# Day0_UmarAlFaruqi_13215057.net
KiCad netlist of a schematic drawn in EAGLE
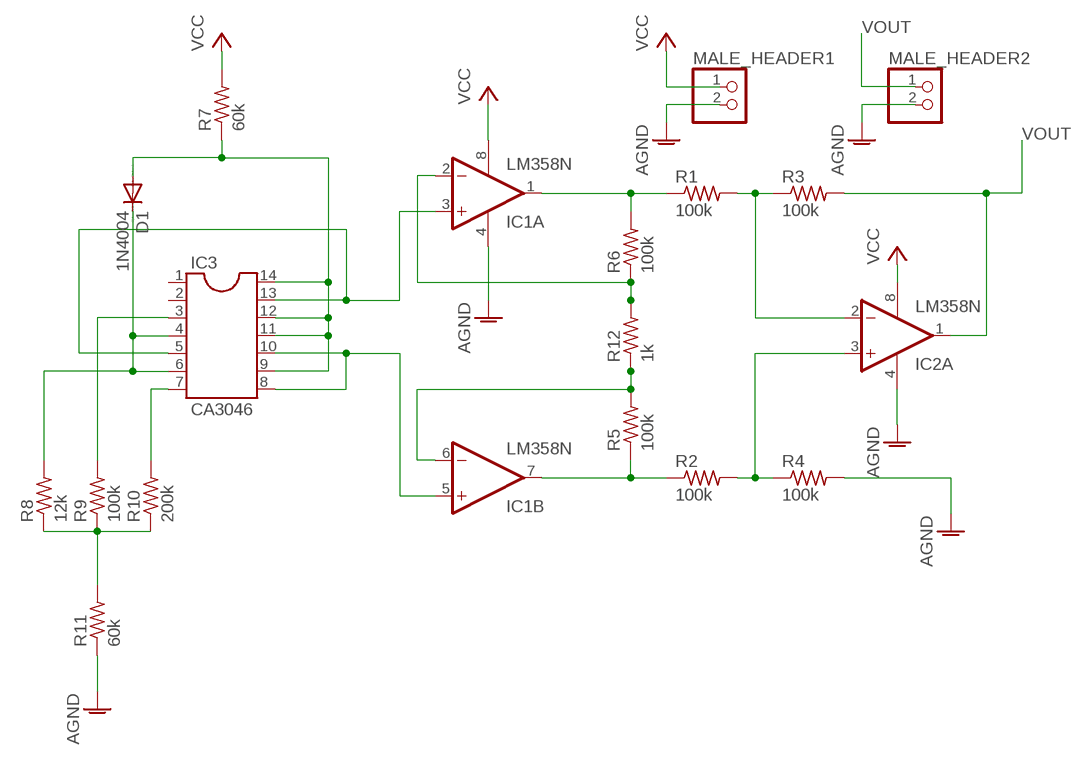
[diagram p0: schematic, sheet 1]

(export (version "E")
  (design (tool "Eeschema 10.0.6"))
  (components
    (comp (ref "D1")
      (value "1N4004")
      (footprint "eagle-import:DO41-10")
      (libsource (lib "eagle-import") (part "1N4004"))
    )
    (comp (ref "IC1")
      (value "LM358N")
      (footprint "eagle-import:DIL08")
      (libsource (lib "eagle-import") (part "LM358N"))
    )
    (comp (ref "IC2")
      (value "LM358N")
      (footprint "eagle-import:DIL08")
      (libsource (lib "eagle-import") (part "LM358N"))
    )
    (comp (ref "IC3")
      (value "CA3046")
      (footprint "eagle-import:DIL14")
      (libsource (lib "eagle-import") (part "DIL14"))
    )
    (comp (ref "MALE_HEADER1")
      (value "PINHD-1X2")
      (footprint "eagle-import:1X02")
      (libsource (lib "eagle-import") (part "PINHD-1X2"))
    )
    (comp (ref "MALE_HEADER2")
      (value "PINHD-1X2")
      (footprint "eagle-import:1X02")
      (libsource (lib "eagle-import") (part "PINHD-1X2"))
    )
    (comp (ref "R1")
      (value "100k")
      (footprint "eagle-import:0204V")
      (libsource (lib "eagle-import") (part "R-US_0204/2V"))
    )
    (comp (ref "R2")
      (value "100k")
      (footprint "eagle-import:0204V")
      (libsource (lib "eagle-import") (part "R-US_0204/2V"))
    )
    (comp (ref "R3")
      (value "100k")
      (footprint "eagle-import:0204V")
      (libsource (lib "eagle-import") (part "R-US_0204/2V"))
    )
    (comp (ref "R4")
      (value "100k")
      (footprint "eagle-import:0204V")
      (libsource (lib "eagle-import") (part "R-US_0204/2V"))
    )
    (comp (ref "R5")
      (value "100k")
      (footprint "eagle-import:0204V")
      (libsource (lib "eagle-import") (part "R-US_0204/2V"))
    )
    (comp (ref "R6")
      (value "100k")
      (footprint "eagle-import:0204V")
      (libsource (lib "eagle-import") (part "R-US_0204/2V"))
    )
    (comp (ref "R7")
      (value "60k")
      (footprint "eagle-import:0204V")
      (libsource (lib "eagle-import") (part "R-US_0204/2V"))
    )
    (comp (ref "R8")
      (value "12k")
      (footprint "eagle-import:0204V")
      (libsource (lib "eagle-import") (part "R-US_0204/2V"))
    )
    (comp (ref "R9")
      (value "100k")
      (footprint "eagle-import:0204V")
      (libsource (lib "eagle-import") (part "R-US_0204/2V"))
    )
    (comp (ref "R10")
      (value "200k")
      (footprint "eagle-import:0204V")
      (libsource (lib "eagle-import") (part "R-US_0204/2V"))
    )
    (comp (ref "R11")
      (value "60k")
      (footprint "eagle-import:0204V")
      (libsource (lib "eagle-import") (part "R-US_0204/2V"))
    )
    (comp (ref "R12")
      (value "1k")
      (footprint "eagle-import:0204V")
      (libsource (lib "eagle-import") (part "R-US_0204/2V"))
    )
  )
  (nets
    (net (code "1") (name "/VOUT") (class "Default")
      (node (ref "IC2") (pin "1") (pinfunction "OUT_1") (pintype "output"))
      (node (ref "MALE_HEADER2") (pin "1") (pinfunction "1_1") (pintype "passive"))
      (node (ref "R3") (pin "2") (pinfunction "2_2") (pintype "passive"))
    )
    (net (code "2") (name "AGND") (class "Default")
      (node (ref "IC1") (pin "4") (pinfunction "V-_4") (pintype "power_in"))
      (node (ref "IC2") (pin "4") (pinfunction "V-_4") (pintype "power_in"))
      (node (ref "MALE_HEADER1") (pin "2") (pinfunction "2_2") (pintype "passive"))
      (node (ref "MALE_HEADER2") (pin "2") (pinfunction "2_2") (pintype "passive"))
      (node (ref "R11") (pin "1") (pinfunction "1_1") (pintype "passive"))
      (node (ref "R4") (pin "2") (pinfunction "2_2") (pintype "passive"))
    )
    (net (code "3") (name "Net-(D1-PadA)") (class "Default")
      (node (ref "D1") (pin "A") (pinfunction "A_A") (pintype "passive"))
      (node (ref "IC3") (pin "11") (pinfunction "11_11") (pintype "passive"))
      (node (ref "IC3") (pin "12") (pinfunction "12_12") (pintype "passive"))
      (node (ref "IC3") (pin "14") (pinfunction "14_14") (pintype "passive"))
      (node (ref "IC3") (pin "9") (pinfunction "9_9") (pintype "passive"))
      (node (ref "R7") (pin "1") (pinfunction "1_1") (pintype "passive"))
    )
    (net (code "4") (name "Net-(D1-PadC)") (class "Default")
      (node (ref "D1") (pin "C") (pinfunction "C_C") (pintype "passive"))
      (node (ref "IC3") (pin "4") (pinfunction "4_4") (pintype "passive"))
      (node (ref "IC3") (pin "6") (pinfunction "6_6") (pintype "passive"))
      (node (ref "R8") (pin "2") (pinfunction "2_2") (pintype "passive"))
    )
    (net (code "5") (name "Net-(IC1A-+IN)") (class "Default")
      (node (ref "IC1") (pin "3") (pinfunction "+IN_3") (pintype "input"))
      (node (ref "IC3") (pin "13") (pinfunction "13_13") (pintype "passive"))
      (node (ref "IC3") (pin "5") (pinfunction "5_5") (pintype "passive"))
    )
    (net (code "6") (name "Net-(IC1A--IN)") (class "Default")
      (node (ref "IC1") (pin "2") (pinfunction "-IN_2") (pintype "input"))
      (node (ref "R12") (pin "2") (pinfunction "2_2") (pintype "passive"))
      (node (ref "R6") (pin "1") (pinfunction "1_1") (pintype "passive"))
    )
    (net (code "7") (name "Net-(IC1A-OUT)") (class "Default")
      (node (ref "IC1") (pin "1") (pinfunction "OUT_1") (pintype "output"))
      (node (ref "R1") (pin "1") (pinfunction "1_1") (pintype "passive"))
      (node (ref "R6") (pin "2") (pinfunction "2_2") (pintype "passive"))
    )
    (net (code "8") (name "Net-(IC1B-+IN)") (class "Default")
      (node (ref "IC1") (pin "5") (pinfunction "+IN_5") (pintype "input"))
      (node (ref "IC3") (pin "10") (pinfunction "10_10") (pintype "passive"))
      (node (ref "IC3") (pin "8") (pinfunction "8_8") (pintype "passive"))
    )
    (net (code "9") (name "Net-(IC1B--IN)") (class "Default")
      (node (ref "IC1") (pin "6") (pinfunction "-IN_6") (pintype "input"))
      (node (ref "R12") (pin "1") (pinfunction "1_1") (pintype "passive"))
      (node (ref "R5") (pin "2") (pinfunction "2_2") (pintype "passive"))
    )
    (net (code "10") (name "Net-(IC1B-OUT)") (class "Default")
      (node (ref "IC1") (pin "7") (pinfunction "OUT_7") (pintype "output"))
      (node (ref "R2") (pin "1") (pinfunction "1_1") (pintype "passive"))
      (node (ref "R5") (pin "1") (pinfunction "1_1") (pintype "passive"))
    )
    (net (code "11") (name "Net-(IC2A-+IN)") (class "Default")
      (node (ref "IC2") (pin "3") (pinfunction "+IN_3") (pintype "input"))
      (node (ref "R2") (pin "2") (pinfunction "2_2") (pintype "passive"))
      (node (ref "R4") (pin "1") (pinfunction "1_1") (pintype "passive"))
    )
    (net (code "12") (name "Net-(IC2A--IN)") (class "Default")
      (node (ref "IC2") (pin "2") (pinfunction "-IN_2") (pintype "input"))
      (node (ref "R1") (pin "2") (pinfunction "2_2") (pintype "passive"))
      (node (ref "R3") (pin "1") (pinfunction "1_1") (pintype "passive"))
    )
    (net (code "13") (name "Net-(IC3-Pad3)") (class "Default")
      (node (ref "IC3") (pin "3") (pinfunction "3_3") (pintype "passive"))
      (node (ref "R9") (pin "2") (pinfunction "2_2") (pintype "passive"))
    )
    (net (code "14") (name "Net-(IC3-Pad7)") (class "Default")
      (node (ref "IC3") (pin "7") (pinfunction "7_7") (pintype "passive"))
      (node (ref "R10") (pin "2") (pinfunction "2_2") (pintype "passive"))
    )
    (net (code "15") (name "Net-(R10-Pad1)") (class "Default")
      (node (ref "R10") (pin "1") (pinfunction "1_1") (pintype "passive"))
      (node (ref "R11") (pin "2") (pinfunction "2_2") (pintype "passive"))
      (node (ref "R8") (pin "1") (pinfunction "1_1") (pintype "passive"))
      (node (ref "R9") (pin "1") (pinfunction "1_1") (pintype "passive"))
    )
    (net (code "16") (name "VCC") (class "Default")
      (node (ref "IC1") (pin "8") (pinfunction "V+_8") (pintype "power_in"))
      (node (ref "IC2") (pin "8") (pinfunction "V+_8") (pintype "power_in"))
      (node (ref "MALE_HEADER1") (pin "1") (pinfunction "1_1") (pintype "passive"))
      (node (ref "R7") (pin "2") (pinfunction "2_2") (pintype "passive"))
    )
    (net (code "17") (name "unconnected-(IC3-Pad1)") (class "Default")
      (node (ref "IC3") (pin "1") (pinfunction "1_1") (pintype "passive"))
    )
    (net (code "18") (name "unconnected-(IC3-Pad2)") (class "Default")
      (node (ref "IC3") (pin "2") (pinfunction "2_2") (pintype "passive"))
    )
  )
)
